# PDOC.net
KiCad netlist of a schematic drawn in Altium Designer
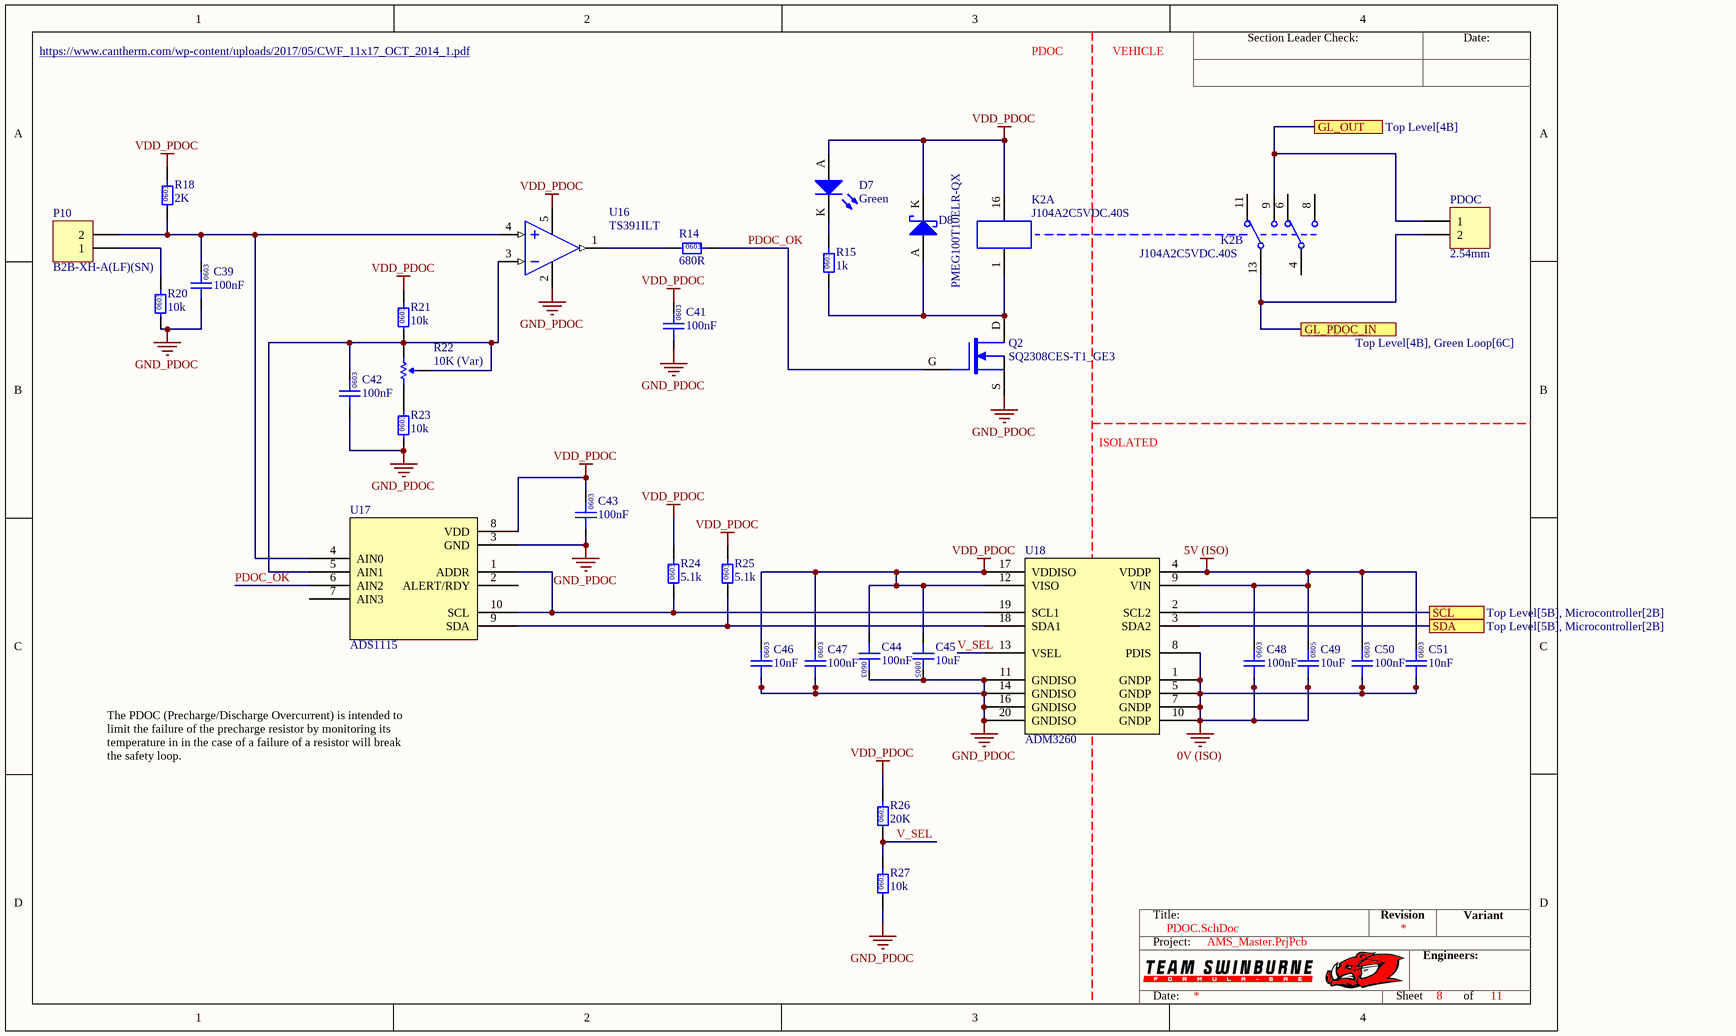
[diagram p0: PDOC.SchDoc]

(export (version "E")
  (design (tool "Eeschema 10.0.6"))
  (components
    (comp (ref "C39")
      (value "100nF")
      (footprint "0603")
      (fields
        (field (name "PART NUMBER") "GCM188L81H104KA57D")
        (field (name "MANUFACTURER") "muRata")
        (field (name "TOLERANCE") "±10%")
      )
      (libsource (lib "ts_standard_library") (part "Capacitor 0603"))
    )
    (comp (ref "C41")
      (value "100nF")
      (footprint "0603")
      (fields
        (field (name "PART NUMBER") "GCM188L81H104KA57D")
        (field (name "MANUFACTURER") "muRata")
        (field (name "TOLERANCE") "±10%")
      )
      (libsource (lib "ts_standard_library") (part "Capacitor 0603"))
    )
    (comp (ref "C42")
      (value "100nF")
      (footprint "0603")
      (fields
        (field (name "PART NUMBER") "GCM188L81H104KA57D")
        (field (name "MANUFACTURER") "muRata")
        (field (name "TOLERANCE") "±10%")
      )
      (libsource (lib "ts_standard_library") (part "Capacitor 0603"))
    )
    (comp (ref "C43")
      (value "100nF")
      (footprint "0603")
      (fields
        (field (name "PART NUMBER") "GCM188L81H104KA57D")
        (field (name "MANUFACTURER") "muRata")
        (field (name "TOLERANCE") "±10%")
      )
      (libsource (lib "ts_standard_library") (part "Capacitor 0603"))
    )
    (comp (ref "C44")
      (value "100nF")
      (footprint "0603")
      (fields
        (field (name "PART NUMBER") "GCM188L81H104KA57D")
        (field (name "MANUFACTURER") "muRata")
        (field (name "TOLERANCE") "±10%")
      )
      (libsource (lib "ts_standard_library") (part "Capacitor 0603"))
    )
    (comp (ref "C45")
      (value "10uF")
      (footprint "0805")
      (fields
        (field (name "PART NUMBER") "GRM21BR6YA106KE43L")
        (field (name "MANUFACTURER") "muRata")
        (field (name "TOLERANCE") "10%")
      )
      (libsource (lib "ts_standard_library") (part "Capacitor 0805"))
    )
    (comp (ref "C46")
      (value "10nF")
      (footprint "0603")
      (fields
        (field (name "PART NUMBER") "GCM188L81H103KA03D")
        (field (name "MANUFACTURER") "muRata")
        (field (name "TOLERANCE") "±10%")
      )
      (libsource (lib "ts_standard_library") (part "Capacitor 0603"))
    )
    (comp (ref "C47")
      (value "100nF")
      (footprint "0603")
      (fields
        (field (name "PART NUMBER") "GCM188L81H104KA57D")
        (field (name "MANUFACTURER") "muRata")
        (field (name "TOLERANCE") "±10%")
      )
      (libsource (lib "ts_standard_library") (part "Capacitor 0603"))
    )
    (comp (ref "C48")
      (value "100nF")
      (footprint "0603")
      (fields
        (field (name "PART NUMBER") "GCM188L81H104KA57D")
        (field (name "MANUFACTURER") "muRata")
        (field (name "TOLERANCE") "±10%")
      )
      (libsource (lib "ts_standard_library") (part "Capacitor 0603"))
    )
    (comp (ref "C49")
      (value "10uF")
      (footprint "0805")
      (fields
        (field (name "PART NUMBER") "GRM21BR6YA106KE43L")
        (field (name "MANUFACTURER") "muRata")
        (field (name "TOLERANCE") "10%")
      )
      (libsource (lib "ts_standard_library") (part "Capacitor 0805"))
    )
    (comp (ref "C50")
      (value "100nF")
      (footprint "0603")
      (fields
        (field (name "PART NUMBER") "GCM188L81H104KA57D")
        (field (name "MANUFACTURER") "muRata")
        (field (name "TOLERANCE") "±10%")
      )
      (libsource (lib "ts_standard_library") (part "Capacitor 0603"))
    )
    (comp (ref "C51")
      (value "10nF")
      (footprint "0603")
      (fields
        (field (name "PART NUMBER") "GCM188L81H103KA03D")
        (field (name "MANUFACTURER") "muRata")
        (field (name "TOLERANCE") "±10%")
      )
      (libsource (lib "ts_standard_library") (part "Capacitor 0603"))
    )
    (comp (ref "D7")
      (value "Green")
      (footprint "0805 LED")
      (description "Green LED Indication - Discrete 1.75V 0805 (2012 Metric)")
      (fields (field (name "PART NUMBER") "SML-210FTT86") (field (name "MANUFACTURER") "ROHM Semiconductor"))
      (libsource (lib "ts_20-standard-library") (part "LED"))
    )
    (comp (ref "D8")
      (value "PMEG100T10ELR-QX")
      (footprint "NXP SOD123W")
      (fields
        (field (name "MANUFACTURER") "Nexperia USA Inc.")
        (field (name "DIGIKEY PART NUMBER") "1727-PMEG100T10ELR-QXCT-ND")
      )
      (libsource (lib "ts_standard_library") (part "Diode (Schottky)"))
    )
    (comp (ref "K2")
      (value "J104A2C5VDC.40S")
      (footprint "TI 2-DIL")
      (description "RELAY GEN PURPOSE DPDT 3A 5V")
      (fields
        (field (name "MANUFACTURER") "CIT Relay and Switch")
        (field (name "DIGIKEY PART NUMBER") "2449-J104A2C5VDC.40S-ND")
      )
      (libsource (lib "") (part "J104A2C5VDC.40S_1"))
    )
    (comp (ref "P10")
      (value "B2B-XH-A(LF)(SN)")
      (footprint "XH 2 PIN VERT")
      (fields (field (name "DIGIKEY PART NUMBER") "455-2247-ND") (field (name "CONTACT") "Tin"))
      (libsource (lib "ts_standard_connectors") (part "Header 1x2"))
    )
    (comp (ref "PDOC")
      (value "2.54mm")
      (footprint "TH 2.54mm Header 1x2")
      (fields (field (name "PART NUMBER") "TH 2.54mm Header 1x2") (field (name "CONTACT") "NA"))
      (libsource (lib "") (part "Header 1x2_1"))
    )
    (comp (ref "Q2")
      (value "SQ2308CES-T1_GE3")
      (footprint "VSHY SOT-23-3")
      (description "MOSFET N-CH 60V 2.3A SOT23")
      (fields
        (field (name "MANUFACTURER") "Vishay Siliconix")
        (field (name "DIGIKEY PART NUMBER") "SQ2308CES-T1_GE3CT-ND")
        (field (name "PUBLISHER") "Altium Limited")
      )
      (libsource (lib "ts_standard_library") (part "MOSFET-N"))
    )
    (comp (ref "R14")
      (value "680R")
      (footprint "0603")
      (fields
        (field (name "PART NUMBER") "RC0603JR-13680RL")
        (field (name "MANUFACTURER") "YAGEO")
        (field (name "TOLERANCE") "0.01")
      )
      (libsource (lib "ts_standard_library") (part "Resistor 0603"))
    )
    (comp (ref "R15")
      (value "1k")
      (footprint "0603")
      (fields
        (field (name "PART NUMBER") "RC0603FR-071KL")
        (field (name "MANUFACTURER") "YAGEO")
        (field (name "TOLERANCE") "0.01")
      )
      (libsource (lib "ts_standard_library") (part "Resistor 0603"))
    )
    (comp (ref "R18")
      (value "2K")
      (footprint "0603")
      (fields
        (field (name "PART NUMBER") "RC0603FR-072KL")
        (field (name "MANUFACTURER") "YAGEO")
        (field (name "TOLERANCE") "0.01")
      )
      (libsource (lib "ts_standard_library") (part "Resistor 0603"))
    )
    (comp (ref "R20")
      (value "10k")
      (footprint "0603")
      (fields
        (field (name "PART NUMBER") "RC0603FR-0710KL")
        (field (name "MANUFACTURER") "YAGEO")
        (field (name "TOLERANCE") "0.01")
      )
      (libsource (lib "ts_standard_library") (part "Resistor 0603"))
    )
    (comp (ref "R21")
      (value "10k")
      (footprint "0603")
      (fields
        (field (name "PART NUMBER") "RC0603FR-0710KL")
        (field (name "MANUFACTURER") "YAGEO")
        (field (name "TOLERANCE") "0.01")
      )
      (libsource (lib "ts_standard_library") (part "Resistor 0603"))
    )
    (comp (ref "R22")
      (value "10K (Var)")
      (footprint "B 3296")
      (fields
        (field (name "PART NUMBER") "3296W-1-103LF")
        (field (name "MANUFACTURER") "Bournes Inc")
        (field (name "TOLERANCE") "0.1")
      )
      (libsource (lib "ts_standard_library") (part "Resistor (Potentiometer)"))
    )
    (comp (ref "R23")
      (value "10k")
      (footprint "0603")
      (fields
        (field (name "PART NUMBER") "RC0603FR-0710KL")
        (field (name "MANUFACTURER") "YAGEO")
        (field (name "TOLERANCE") "0.01")
      )
      (libsource (lib "ts_standard_library") (part "Resistor 0603"))
    )
    (comp (ref "R24")
      (value "5.1k")
      (footprint "0603")
      (fields
        (field (name "PART NUMBER") "RC0603JR-075K1L")
        (field (name "MANUFACTURER") "YAGEO")
        (field (name "TOLERANCE") "0.01")
      )
      (libsource (lib "ts_standard_library") (part "Resistor 0603"))
    )
    (comp (ref "R25")
      (value "5.1k")
      (footprint "0603")
      (fields
        (field (name "PART NUMBER") "RC0603JR-075K1L")
        (field (name "MANUFACTURER") "YAGEO")
        (field (name "TOLERANCE") "0.01")
      )
      (libsource (lib "ts_standard_library") (part "Resistor 0603"))
    )
    (comp (ref "R26")
      (value "20K")
      (footprint "0603")
      (fields
        (field (name "PART NUMBER") "RC0603FR-0720KL")
        (field (name "MANUFACTURER") "YAGEO")
        (field (name "TOLERANCE") "0.01")
      )
      (libsource (lib "ts_standard_library") (part "Resistor 0603"))
    )
    (comp (ref "R27")
      (value "10k")
      (footprint "0603")
      (fields
        (field (name "PART NUMBER") "RC0603FR-0710KL")
        (field (name "MANUFACTURER") "YAGEO")
        (field (name "TOLERANCE") "0.01")
      )
      (libsource (lib "ts_standard_library") (part "Resistor 0603"))
    )
    (comp (ref "U16")
      (value "TS391ILT")
      (footprint "ON SOT-23-5")
      (description "IC COMP LO PWR SGL V SOT 23-5L")
      (libsource (lib "Team Swinburne") (part "TS391ILT"))
    )
    (comp (ref "U17")
      (value "ADS1115")
      (footprint "TI 10-VSSOP")
      (description "16 Bit Analog to Digital Converter 2, 4 Input 1 Sigma-Delta 10-VSSOP")
      (fields
        (field (name "MANUFACTURER") "Texas Instruments")
        (field (name "DIGIKEY PART NUMBER") "296-38849-1-ND")
      )
      (libsource (lib "ts_standard_library") (part "ADS1115"))
    )
    (comp (ref "U18")
      (value "ADM3260")
      (footprint "AD 20-SSOP")
      (description "I²C Digital Isolator 2500Vrms 2 Channel 25kV/µs CMTI 20-SSOP (0.209\", 5.30mm Width)")
      (libsource (lib "Team Swinburne") (part "ADM3260"))
    )
  )
  (nets
    (net (code "1") (name "/GL_OUT") (class "Default")
      (node (ref "K2") (pin "9") (pinfunction "9_9") (pintype "passive"))
      (node (ref "PDOC") (pin "1") (pinfunction "1_1") (pintype "passive"))
    )
    (net (code "2") (name "/GL_PDOC_IN") (class "Default")
      (node (ref "K2") (pin "13") (pinfunction "13_13") (pintype "passive"))
      (node (ref "PDOC") (pin "2") (pinfunction "2_2") (pintype "passive"))
    )
    (net (code "3") (name "/PDOC_OK") (class "Default")
      (node (ref "Q2") (pin "G") (pinfunction "G_G") (pintype "passive"))
      (node (ref "R14") (pin "2") (pinfunction "2_2") (pintype "passive"))
      (node (ref "U17") (pin "6") (pinfunction "AIN2_6") (pintype "passive"))
    )
    (net (code "4") (name "/SCL") (class "Default")
      (node (ref "U18") (pin "2") (pinfunction "SCL2_2") (pintype "passive"))
    )
    (net (code "5") (name "/SDA") (class "Default")
      (node (ref "U18") (pin "3") (pinfunction "SDA2_3") (pintype "passive"))
    )
    (net (code "6") (name "/V_SEL") (class "Default")
      (node (ref "R26") (pin "1") (pinfunction "1_1") (pintype "passive"))
      (node (ref "R27") (pin "2") (pinfunction "2_2") (pintype "passive"))
      (node (ref "U18") (pin "13") (pinfunction "VSEL_13") (pintype "passive"))
    )
    (net (code "7") (name "0V (ISO)") (class "Default")
      (node (ref "C48") (pin "1") (pinfunction "1_1") (pintype "passive"))
      (node (ref "C49") (pin "1") (pinfunction "1_1") (pintype "passive"))
      (node (ref "C50") (pin "1") (pinfunction "1_1") (pintype "passive"))
      (node (ref "C51") (pin "1") (pinfunction "1_1") (pintype "passive"))
      (node (ref "U18") (pin "1") (pinfunction "GNDP_1") (pintype "passive"))
      (node (ref "U18") (pin "10") (pinfunction "GNDP_10") (pintype "passive"))
      (node (ref "U18") (pin "5") (pinfunction "GNDP_5") (pintype "passive"))
      (node (ref "U18") (pin "7") (pinfunction "GNDP_7") (pintype "passive"))
      (node (ref "U18") (pin "8") (pinfunction "PDIS_8") (pintype "passive"))
    )
    (net (code "8") (name "5V (ISO)") (class "Default")
      (node (ref "C48") (pin "2") (pinfunction "2_2") (pintype "passive"))
      (node (ref "C49") (pin "2") (pinfunction "2_2") (pintype "passive"))
      (node (ref "C50") (pin "2") (pinfunction "2_2") (pintype "passive"))
      (node (ref "C51") (pin "2") (pinfunction "2_2") (pintype "passive"))
      (node (ref "U18") (pin "4") (pinfunction "VDDP_4") (pintype "passive"))
      (node (ref "U18") (pin "9") (pinfunction "VIN_9") (pintype "passive"))
    )
    (net (code "9") (name "GND_PDOC") (class "Default")
      (node (ref "C39") (pin "1") (pinfunction "1_1") (pintype "passive"))
      (node (ref "C41") (pin "1") (pinfunction "1_1") (pintype "passive"))
      (node (ref "C42") (pin "1") (pinfunction "1_1") (pintype "passive"))
      (node (ref "C43") (pin "1") (pinfunction "1_1") (pintype "passive"))
      (node (ref "C44") (pin "2") (pinfunction "2_2") (pintype "passive"))
      (node (ref "C45") (pin "2") (pinfunction "2_2") (pintype "passive"))
      (node (ref "C46") (pin "1") (pinfunction "1_1") (pintype "passive"))
      (node (ref "C47") (pin "1") (pinfunction "1_1") (pintype "passive"))
      (node (ref "Q2") (pin "S") (pinfunction "S_S") (pintype "passive"))
      (node (ref "R20") (pin "1") (pinfunction "1_1") (pintype "passive"))
      (node (ref "R23") (pin "1") (pinfunction "1_1") (pintype "passive"))
      (node (ref "R27") (pin "1") (pinfunction "1_1") (pintype "passive"))
      (node (ref "U16") (pin "2") (pinfunction "VCC-_2") (pintype "power_in"))
      (node (ref "U17") (pin "3") (pinfunction "GND_3") (pintype "passive"))
      (node (ref "U18") (pin "11") (pinfunction "GNDISO_11") (pintype "passive"))
      (node (ref "U18") (pin "14") (pinfunction "GNDISO_14") (pintype "passive"))
      (node (ref "U18") (pin "16") (pinfunction "GNDISO_16") (pintype "passive"))
      (node (ref "U18") (pin "20") (pinfunction "GNDISO_20") (pintype "passive"))
    )
    (net (code "10") (name "Net-(D7-PadK)") (class "Default")
      (node (ref "D7") (pin "K") (pinfunction "K_K") (pintype "passive"))
      (node (ref "R15") (pin "2") (pinfunction "2_2") (pintype "passive"))
    )
    (net (code "11") (name "Net-(D8-PadA)") (class "Default")
      (node (ref "D8") (pin "A") (pinfunction "A_A") (pintype "passive"))
      (node (ref "K2") (pin "1") (pinfunction "1_1") (pintype "passive"))
      (node (ref "Q2") (pin "D") (pinfunction "D_D") (pintype "passive"))
      (node (ref "R15") (pin "1") (pinfunction "1_1") (pintype "passive"))
    )
    (net (code "12") (name "Net-(P10-Pad1)") (class "Default")
      (node (ref "P10") (pin "1") (pinfunction "1_1") (pintype "passive"))
      (node (ref "R20") (pin "2") (pinfunction "2_2") (pintype "passive"))
    )
    (net (code "13") (name "Net-(R22-CCW)") (class "Default")
      (node (ref "C42") (pin "2") (pinfunction "2_2") (pintype "passive"))
      (node (ref "R21") (pin "1") (pinfunction "1_1") (pintype "passive"))
      (node (ref "R22") (pin "1") (pinfunction "CCW_1") (pintype "passive"))
      (node (ref "R22") (pin "2") (pinfunction "Wiper_2") (pintype "passive"))
      (node (ref "U16") (pin "3") (pinfunction "IN-_3") (pintype "input"))
      (node (ref "U17") (pin "5") (pinfunction "AIN1_5") (pintype "passive"))
    )
    (net (code "14") (name "Net-(R22-CW)") (class "Default")
      (node (ref "R22") (pin "3") (pinfunction "CW_3") (pintype "passive"))
      (node (ref "R23") (pin "2") (pinfunction "2_2") (pintype "passive"))
    )
    (net (code "15") (name "Net-(U16-IIN+)") (class "Default")
      (node (ref "C39") (pin "2") (pinfunction "2_2") (pintype "passive"))
      (node (ref "P10") (pin "2") (pinfunction "2_2") (pintype "passive"))
      (node (ref "R18") (pin "1") (pinfunction "1_1") (pintype "passive"))
      (node (ref "U16") (pin "4") (pinfunction "IIN+_4") (pintype "input"))
      (node (ref "U17") (pin "4") (pinfunction "AIN0_4") (pintype "passive"))
    )
    (net (code "16") (name "Net-(U16-OUT)") (class "Default")
      (node (ref "R14") (pin "1") (pinfunction "1_1") (pintype "passive"))
      (node (ref "U16") (pin "1") (pinfunction "OUT_1") (pintype "output"))
    )
    (net (code "17") (name "Net-(U17-ADDR)") (class "Default")
      (node (ref "R24") (pin "1") (pinfunction "1_1") (pintype "passive"))
      (node (ref "U17") (pin "1") (pinfunction "ADDR_1") (pintype "passive"))
      (node (ref "U17") (pin "10") (pinfunction "SCL_10") (pintype "passive"))
      (node (ref "U18") (pin "19") (pinfunction "SCL1_19") (pintype "passive"))
    )
    (net (code "18") (name "Net-(U17-SDA)") (class "Default")
      (node (ref "R25") (pin "1") (pinfunction "1_1") (pintype "passive"))
      (node (ref "U17") (pin "9") (pinfunction "SDA_9") (pintype "passive"))
      (node (ref "U18") (pin "18") (pinfunction "SDA1_18") (pintype "passive"))
    )
    (net (code "19") (name "VDD_PDOC") (class "Default")
      (node (ref "C41") (pin "2") (pinfunction "2_2") (pintype "passive"))
      (node (ref "C43") (pin "2") (pinfunction "2_2") (pintype "passive"))
      (node (ref "C44") (pin "1") (pinfunction "1_1") (pintype "passive"))
      (node (ref "C45") (pin "1") (pinfunction "1_1") (pintype "passive"))
      (node (ref "C46") (pin "2") (pinfunction "2_2") (pintype "passive"))
      (node (ref "C47") (pin "2") (pinfunction "2_2") (pintype "passive"))
      (node (ref "D7") (pin "A") (pinfunction "A_A") (pintype "passive"))
      (node (ref "D8") (pin "K") (pinfunction "K_K") (pintype "passive"))
      (node (ref "K2") (pin "16") (pinfunction "16_16") (pintype "passive"))
      (node (ref "R18") (pin "2") (pinfunction "2_2") (pintype "passive"))
      (node (ref "R21") (pin "2") (pinfunction "2_2") (pintype "passive"))
      (node (ref "R24") (pin "2") (pinfunction "2_2") (pintype "passive"))
      (node (ref "R25") (pin "2") (pinfunction "2_2") (pintype "passive"))
      (node (ref "R26") (pin "2") (pinfunction "2_2") (pintype "passive"))
      (node (ref "U16") (pin "5") (pinfunction "VCC+_5") (pintype "power_in"))
      (node (ref "U17") (pin "8") (pinfunction "VDD_8") (pintype "passive"))
      (node (ref "U18") (pin "12") (pinfunction "VISO_12") (pintype "passive"))
      (node (ref "U18") (pin "17") (pinfunction "VDDISO_17") (pintype "passive"))
    )
    (net (code "20") (name "unconnected-(K2-Pad4)") (class "Default")
      (node (ref "K2") (pin "4") (pinfunction "4_4") (pintype "passive"))
    )
    (net (code "21") (name "unconnected-(K2-Pad6)") (class "Default")
      (node (ref "K2") (pin "6") (pinfunction "6_6") (pintype "passive"))
    )
    (net (code "22") (name "unconnected-(K2-Pad8)") (class "Default")
      (node (ref "K2") (pin "8") (pinfunction "8_8") (pintype "passive"))
    )
    (net (code "23") (name "unconnected-(K2-Pad11)") (class "Default")
      (node (ref "K2") (pin "11") (pinfunction "11_11") (pintype "passive"))
    )
    (net (code "24") (name "unconnected-(U17-AIN3-Pad7)") (class "Default")
      (node (ref "U17") (pin "7") (pinfunction "AIN3_7") (pintype "passive"))
    )
    (net (code "25") (name "unconnected-(U17-ALERT{slash}RDY-Pad2)") (class "Default")
      (node (ref "U17") (pin "2") (pinfunction "ALERT/RDY_2") (pintype "passive"))
    )
  )
)
